# DoseManager.net
KiCad netlist of a schematic drawn in EAGLE
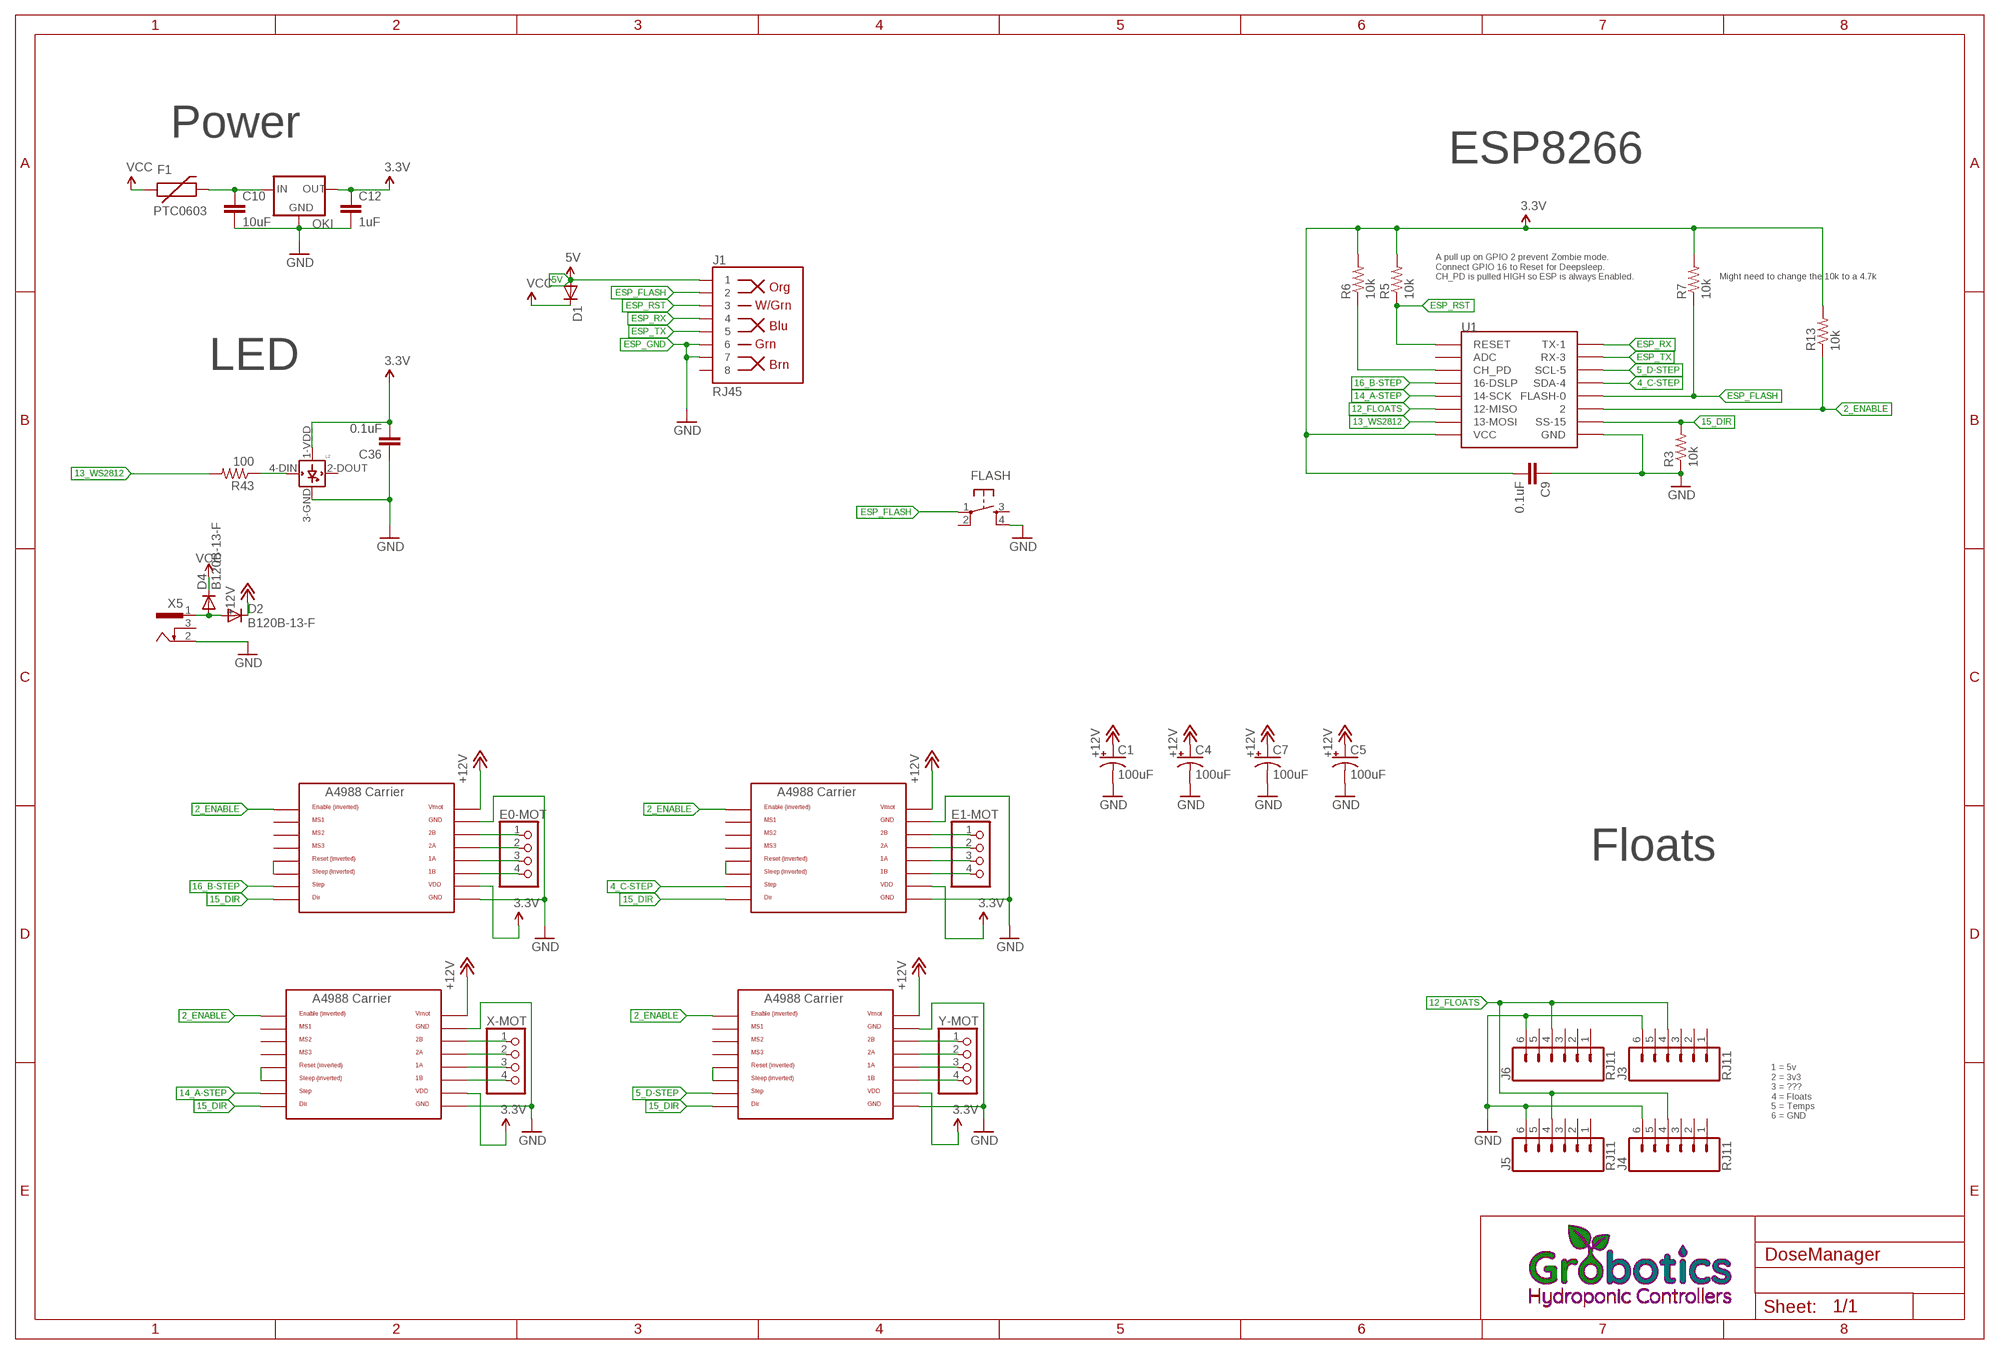
[diagram p0: schematic, sheet 1]

(export (version "E")
  (design (tool "Eeschema 10.0.6"))
  (components
    (comp (ref "C1")
      (value "100uF")
      (footprint "eagle-import:153CLV-0605")
      (libsource (lib "eagle-import") (part "CPOL-US153CLV-0605"))
    )
    (comp (ref "C4")
      (value "100uF")
      (footprint "eagle-import:153CLV-0605")
      (libsource (lib "eagle-import") (part "CPOL-US153CLV-0605"))
    )
    (comp (ref "C5")
      (value "100uF")
      (footprint "eagle-import:153CLV-0605")
      (libsource (lib "eagle-import") (part "CPOL-US153CLV-0605"))
    )
    (comp (ref "C7")
      (value "100uF")
      (footprint "eagle-import:153CLV-0605")
      (libsource (lib "eagle-import") (part "CPOL-US153CLV-0605"))
    )
    (comp (ref "C9")
      (value "0.1uF")
      (footprint "eagle-import:0805")
      (libsource (lib "eagle-import") (part "CAP0805"))
    )
    (comp (ref "C10")
      (value "10uF")
      (footprint "eagle-import:1206")
      (libsource (lib "eagle-import") (part "CAP1206"))
    )
    (comp (ref "C12")
      (value "1uF")
      (footprint "eagle-import:0805")
      (libsource (lib "eagle-import") (part "CAP0805"))
    )
    (comp (ref "C36")
      (value "0.1uF")
      (footprint "eagle-import:0805")
      (libsource (lib "eagle-import") (part "CAP0805"))
    )
    (comp (ref "D1")
      (value "DIODESOD")
      (footprint "eagle-import:SOD-323")
      (libsource (lib "eagle-import") (part "DIODESOD"))
    )
    (comp (ref "D2")
      (value "B120B-13-F")
      (footprint "eagle-import:SMB-DIODE")
      (libsource (lib "eagle-import") (part "DIODESMB"))
    )
    (comp (ref "D4")
      (value "B120B-13-F")
      (footprint "eagle-import:SMB-DIODE")
      (libsource (lib "eagle-import") (part "DIODESMB"))
    )
    (comp (ref "E0-MOT")
      (value "PINHD-1X4")
      (footprint "eagle-import:1X04")
      (libsource (lib "eagle-import") (part "PINHD-1X4"))
    )
    (comp (ref "E1-MOT")
      (value "PINHD-1X4")
      (footprint "eagle-import:1X04")
      (libsource (lib "eagle-import") (part "PINHD-1X4"))
    )
    (comp (ref "F1")
      (value "PTC0603")
      (footprint "eagle-import:0603")
      (libsource (lib "eagle-import") (part "PTC0603"))
    )
    (comp (ref "FLASH")
      (value "TAC_SWITCHSMD")
      (footprint "eagle-import:TACTILE_SWITCH_SMD")
      (libsource (lib "eagle-import") (part "TAC_SWITCHSMD"))
    )
    (comp (ref "J1")
      (value "RJ45")
      (footprint "eagle-import:RJ45-8")
      (libsource (lib "eagle-import") (part "RJ45-8"))
    )
    (comp (ref "J3")
      (value "RJ11")
      (footprint "eagle-import:RJ11-6")
      (fields (field (name "PROD_ID") "CONN-08590") (field (name "SF_ID") "PRT-00132"))
      (libsource (lib "eagle-import") (part "RJ11-6"))
    )
    (comp (ref "J4")
      (value "RJ11")
      (footprint "eagle-import:RJ11-6")
      (fields (field (name "PROD_ID") "CONN-08590") (field (name "SF_ID") "PRT-00132"))
      (libsource (lib "eagle-import") (part "RJ11-6"))
    )
    (comp (ref "J5")
      (value "RJ11")
      (footprint "eagle-import:RJ11-6")
      (fields (field (name "PROD_ID") "CONN-08590") (field (name "SF_ID") "PRT-00132"))
      (libsource (lib "eagle-import") (part "RJ11-6"))
    )
    (comp (ref "J6")
      (value "RJ11")
      (footprint "eagle-import:RJ11-6")
      (fields (field (name "PROD_ID") "CONN-08590") (field (name "SF_ID") "PRT-00132"))
      (libsource (lib "eagle-import") (part "RJ11-6"))
    )
    (comp (ref "L2")
      (value "WS2812B")
      (footprint "eagle-import:WS2812B")
      (libsource (lib "eagle-import") (part "WS2812B"))
    )
    (comp (ref "OKI")
      (value "78XXS")
      (footprint "eagle-import:78XXS")
      (libsource (lib "eagle-import") (part "78XXS"))
    )
    (comp (ref "R3")
      (value "10k")
      (footprint "eagle-import:0805")
      (libsource (lib "eagle-import") (part "RESISTOR0805"))
    )
    (comp (ref "R5")
      (value "10k")
      (footprint "eagle-import:0805")
      (libsource (lib "eagle-import") (part "RESISTOR0805"))
    )
    (comp (ref "R6")
      (value "10k")
      (footprint "eagle-import:0805")
      (libsource (lib "eagle-import") (part "RESISTOR0805"))
    )
    (comp (ref "R7")
      (value "10k")
      (footprint "eagle-import:0805")
      (libsource (lib "eagle-import") (part "RESISTOR0805"))
    )
    (comp (ref "R13")
      (value "10k")
      (footprint "eagle-import:0805")
      (libsource (lib "eagle-import") (part "RESISTOR0805"))
    )
    (comp (ref "R43")
      (value "100")
      (footprint "eagle-import:0805")
      (libsource (lib "eagle-import") (part "RESISTOR0805"))
    )
    (comp (ref "U$1")
      (value "A4988BREAKOUT")
      (footprint "eagle-import:A4988BREAKOUT")
      (libsource (lib "eagle-import") (part "A4988BREAKOUT"))
    )
    (comp (ref "U$2")
      (value "LOGO_GROBOTICS-S")
      (footprint "eagle-import:GROBOTICS-S")
      (libsource (lib "eagle-import") (part "LOGO_GROBOTICS-S"))
    )
    (comp (ref "U$5")
      (value "A4988BREAKOUT")
      (footprint "eagle-import:A4988BREAKOUT")
      (libsource (lib "eagle-import") (part "A4988BREAKOUT"))
    )
    (comp (ref "U$6")
      (value "A4988BREAKOUT")
      (footprint "eagle-import:A4988BREAKOUT")
      (libsource (lib "eagle-import") (part "A4988BREAKOUT"))
    )
    (comp (ref "U$7")
      (value "A4988BREAKOUT")
      (footprint "eagle-import:A4988BREAKOUT")
      (libsource (lib "eagle-import") (part "A4988BREAKOUT"))
    )
    (comp (ref "U1")
      (value "ESP12SMD")
      (footprint "eagle-import:ESP12-SMD")
      (libsource (lib "eagle-import") (part "ESP12SMD"))
    )
    (comp (ref "X-MOT")
      (value "PINHD-1X4")
      (footprint "eagle-import:1X04")
      (libsource (lib "eagle-import") (part "PINHD-1X4"))
    )
    (comp (ref "X5")
      (value "733980-62")
      (footprint "eagle-import:733980-62")
      (libsource (lib "eagle-import") (part "73398?0-62"))
    )
    (comp (ref "Y-MOT")
      (value "PINHD-1X4")
      (footprint "eagle-import:1X04")
      (libsource (lib "eagle-import") (part "PINHD-1X4"))
    )
  )
  (nets
    (net (code "1") (name "+12V") (class "Default")
      (node (ref "C1") (pin "+") (pinfunction "+_+") (pintype "passive"))
      (node (ref "C4") (pin "+") (pinfunction "+_+") (pintype "passive"))
      (node (ref "C5") (pin "+") (pinfunction "+_+") (pintype "passive"))
      (node (ref "C7") (pin "+") (pinfunction "+_+") (pintype "passive"))
      (node (ref "D2") (pin "C") (pinfunction "C_C") (pintype "passive"))
      (node (ref "U$1") (pin "VMOT") (pinfunction "VMOT_VMOT") (pintype "power_in"))
      (node (ref "U$5") (pin "VMOT") (pinfunction "VMOT_VMOT") (pintype "power_in"))
      (node (ref "U$6") (pin "VMOT") (pinfunction "VMOT_VMOT") (pintype "power_in"))
      (node (ref "U$7") (pin "VMOT") (pinfunction "VMOT_VMOT") (pintype "power_in"))
    )
    (net (code "2") (name "2_ENABLE") (class "Default")
      (node (ref "R13") (pin "1") (pinfunction "1_1") (pintype "passive"))
      (node (ref "U$1") (pin "EN") (pinfunction "EN_EN") (pintype "input"))
      (node (ref "U$5") (pin "EN") (pinfunction "EN_EN") (pintype "input"))
      (node (ref "U$6") (pin "EN") (pinfunction "EN_EN") (pintype "input"))
      (node (ref "U$7") (pin "EN") (pinfunction "EN_EN") (pintype "input"))
      (node (ref "U1") (pin "GPIO2") (pinfunction "2_GPIO2") (pintype "bidirectional"))
    )
    (net (code "3") (name "3.3V") (class "Default")
      (node (ref "C12") (pin "1") (pinfunction "1_1") (pintype "passive"))
      (node (ref "C36") (pin "2") (pinfunction "2_2") (pintype "passive"))
      (node (ref "C9") (pin "2") (pinfunction "2_2") (pintype "passive"))
      (node (ref "L2") (pin "1-VDD") (pinfunction "VDD_1-VDD") (pintype "bidirectional"))
      (node (ref "OKI") (pin "OUT") (pinfunction "OUT_OUT") (pintype "passive"))
      (node (ref "R13") (pin "2") (pinfunction "2_2") (pintype "passive"))
      (node (ref "R5") (pin "2") (pinfunction "2_2") (pintype "passive"))
      (node (ref "R6") (pin "2") (pinfunction "2_2") (pintype "passive"))
      (node (ref "R7") (pin "2") (pinfunction "2_2") (pintype "passive"))
      (node (ref "U$1") (pin "VDD") (pinfunction "VDD_VDD") (pintype "power_in"))
      (node (ref "U$5") (pin "VDD") (pinfunction "VDD_VDD") (pintype "power_in"))
      (node (ref "U$6") (pin "VDD") (pinfunction "VDD_VDD") (pintype "power_in"))
      (node (ref "U$7") (pin "VDD") (pinfunction "VDD_VDD") (pintype "power_in"))
      (node (ref "U1") (pin "VCC") (pinfunction "VCC_VCC") (pintype "bidirectional"))
    )
    (net (code "4") (name "4_C-STEP") (class "Default")
      (node (ref "U$5") (pin "STEP") (pinfunction "STEP_STEP") (pintype "input"))
      (node (ref "U1") (pin "GPIO4") (pinfunction "SDA-4_GPIO4") (pintype "bidirectional"))
    )
    (net (code "5") (name "5V") (class "Default")
      (node (ref "D1") (pin "2") (pinfunction "A_2") (pintype "passive"))
      (node (ref "J1") (pin "1") (pinfunction "1_1") (pintype "bidirectional"))
    )
    (net (code "6") (name "5_D-STEP") (class "Default")
      (node (ref "U$7") (pin "STEP") (pinfunction "STEP_STEP") (pintype "input"))
      (node (ref "U1") (pin "GPIO5") (pinfunction "SCL-5_GPIO5") (pintype "bidirectional"))
    )
    (net (code "7") (name "12_FLOATS") (class "Default")
      (node (ref "J3") (pin "4") (pinfunction "4_4") (pintype "passive"))
      (node (ref "J4") (pin "4") (pinfunction "4_4") (pintype "passive"))
      (node (ref "J5") (pin "4") (pinfunction "4_4") (pintype "passive"))
      (node (ref "J6") (pin "4") (pinfunction "4_4") (pintype "passive"))
      (node (ref "U1") (pin "GPIO12") (pinfunction "12-MISO_GPIO12") (pintype "bidirectional"))
    )
    (net (code "8") (name "13_WS2812") (class "Default")
      (node (ref "R43") (pin "2") (pinfunction "2_2") (pintype "passive"))
      (node (ref "U1") (pin "GPIO13") (pinfunction "13-MOSI_GPIO13") (pintype "bidirectional"))
    )
    (net (code "9") (name "14_A-STEP") (class "Default")
      (node (ref "U$6") (pin "STEP") (pinfunction "STEP_STEP") (pintype "input"))
      (node (ref "U1") (pin "GPIO14") (pinfunction "14-SCK_GPIO14") (pintype "bidirectional"))
    )
    (net (code "10") (name "15_DIR") (class "Default")
      (node (ref "R3") (pin "2") (pinfunction "2_2") (pintype "passive"))
      (node (ref "U$1") (pin "DIR") (pinfunction "DIR_DIR") (pintype "input"))
      (node (ref "U$5") (pin "DIR") (pinfunction "DIR_DIR") (pintype "input"))
      (node (ref "U$6") (pin "DIR") (pinfunction "DIR_DIR") (pintype "input"))
      (node (ref "U$7") (pin "DIR") (pinfunction "DIR_DIR") (pintype "input"))
      (node (ref "U1") (pin "GPIO15") (pinfunction "SS-15_GPIO15") (pintype "bidirectional"))
    )
    (net (code "11") (name "16_B-STEP") (class "Default")
      (node (ref "U$1") (pin "STEP") (pinfunction "STEP_STEP") (pintype "input"))
      (node (ref "U1") (pin "GPIO16") (pinfunction "16-DSLP_GPIO16") (pintype "bidirectional"))
    )
    (net (code "12") (name "ESP_FLASH") (class "Default")
      (node (ref "FLASH") (pin "1") (pinfunction "1_1") (pintype "passive"))
      (node (ref "J1") (pin "2") (pinfunction "2_2") (pintype "bidirectional"))
      (node (ref "R7") (pin "1") (pinfunction "1_1") (pintype "passive"))
      (node (ref "U1") (pin "GPIO0") (pinfunction "FLASH-0_GPIO0") (pintype "bidirectional"))
    )
    (net (code "13") (name "ESP_GND") (class "Default")
      (node (ref "C1") (pin "-") (pinfunction "-_-") (pintype "passive"))
      (node (ref "C10") (pin "2") (pinfunction "2_2") (pintype "passive"))
      (node (ref "C12") (pin "2") (pinfunction "2_2") (pintype "passive"))
      (node (ref "C36") (pin "1") (pinfunction "1_1") (pintype "passive"))
      (node (ref "C4") (pin "-") (pinfunction "-_-") (pintype "passive"))
      (node (ref "C5") (pin "-") (pinfunction "-_-") (pintype "passive"))
      (node (ref "C7") (pin "-") (pinfunction "-_-") (pintype "passive"))
      (node (ref "C9") (pin "1") (pinfunction "1_1") (pintype "passive"))
      (node (ref "FLASH") (pin "4") (pinfunction "4_4") (pintype "passive"))
      (node (ref "J1") (pin "6") (pinfunction "6_6") (pintype "bidirectional"))
      (node (ref "J1") (pin "7") (pinfunction "7_7") (pintype "bidirectional"))
      (node (ref "J3") (pin "6") (pinfunction "6_6") (pintype "passive"))
      (node (ref "J4") (pin "6") (pinfunction "6_6") (pintype "passive"))
      (node (ref "J5") (pin "6") (pinfunction "6_6") (pintype "passive"))
      (node (ref "J6") (pin "6") (pinfunction "6_6") (pintype "passive"))
      (node (ref "L2") (pin "3-GND") (pinfunction "GND_3-GND") (pintype "bidirectional"))
      (node (ref "OKI") (pin "GND") (pinfunction "GND_GND") (pintype "input"))
      (node (ref "R3") (pin "1") (pinfunction "1_1") (pintype "passive"))
      (node (ref "U$1") (pin "GND") (pinfunction "GND_GND") (pintype "power_in"))
      (node (ref "U$1") (pin "GND@0") (pinfunction "GND_GND@0") (pintype "power_in"))
      (node (ref "U$5") (pin "GND") (pinfunction "GND_GND") (pintype "power_in"))
      (node (ref "U$5") (pin "GND@0") (pinfunction "GND_GND@0") (pintype "power_in"))
      (node (ref "U$6") (pin "GND") (pinfunction "GND_GND") (pintype "power_in"))
      (node (ref "U$6") (pin "GND@0") (pinfunction "GND_GND@0") (pintype "power_in"))
      (node (ref "U$7") (pin "GND") (pinfunction "GND_GND") (pintype "power_in"))
      (node (ref "U$7") (pin "GND@0") (pinfunction "GND_GND@0") (pintype "power_in"))
      (node (ref "U1") (pin "GND") (pinfunction "GND_GND") (pintype "bidirectional"))
      (node (ref "X5") (pin "2") (pinfunction "2_2") (pintype "passive"))
    )
    (net (code "14") (name "ESP_RST") (class "Default")
      (node (ref "J1") (pin "3") (pinfunction "3_3") (pintype "bidirectional"))
      (node (ref "R5") (pin "1") (pinfunction "1_1") (pintype "passive"))
      (node (ref "U1") (pin "RESET") (pinfunction "RESET_RESET") (pintype "bidirectional"))
    )
    (net (code "15") (name "ESP_RX") (class "Default")
      (node (ref "J1") (pin "4") (pinfunction "4_4") (pintype "bidirectional"))
      (node (ref "U1") (pin "TXD0") (pinfunction "TX-1_TXD0") (pintype "bidirectional"))
    )
    (net (code "16") (name "ESP_TX") (class "Default")
      (node (ref "J1") (pin "5") (pinfunction "5_5") (pintype "bidirectional"))
      (node (ref "U1") (pin "RXD0") (pinfunction "RX-3_RXD0") (pintype "bidirectional"))
    )
    (net (code "17") (name "Net-(C10-Pad1)") (class "Default")
      (node (ref "C10") (pin "1") (pinfunction "1_1") (pintype "passive"))
      (node (ref "F1") (pin "2") (pinfunction "2_2") (pintype "bidirectional"))
      (node (ref "OKI") (pin "IN") (pinfunction "IN_IN") (pintype "input"))
    )
    (net (code "18") (name "Net-(D2-PadA)") (class "Default")
      (node (ref "D2") (pin "A") (pinfunction "A_A") (pintype "passive"))
      (node (ref "D4") (pin "A") (pinfunction "A_A") (pintype "passive"))
      (node (ref "X5") (pin "1") (pinfunction "1_1") (pintype "passive"))
    )
    (net (code "19") (name "Net-(E0-MOT-Pad1)") (class "Default")
      (node (ref "E0-MOT") (pin "1") (pinfunction "1_1") (pintype "passive"))
      (node (ref "U$1") (pin "2B") (pinfunction "2B_2B") (pintype "output"))
    )
    (net (code "20") (name "Net-(E0-MOT-Pad2)") (class "Default")
      (node (ref "E0-MOT") (pin "2") (pinfunction "2_2") (pintype "passive"))
      (node (ref "U$1") (pin "2A") (pinfunction "2A_2A") (pintype "output"))
    )
    (net (code "21") (name "Net-(E0-MOT-Pad3)") (class "Default")
      (node (ref "E0-MOT") (pin "3") (pinfunction "3_3") (pintype "passive"))
      (node (ref "U$1") (pin "1A") (pinfunction "1A_1A") (pintype "output"))
    )
    (net (code "22") (name "Net-(E0-MOT-Pad4)") (class "Default")
      (node (ref "E0-MOT") (pin "4") (pinfunction "4_4") (pintype "passive"))
      (node (ref "U$1") (pin "1B") (pinfunction "1B_1B") (pintype "output"))
    )
    (net (code "23") (name "Net-(E1-MOT-Pad1)") (class "Default")
      (node (ref "E1-MOT") (pin "1") (pinfunction "1_1") (pintype "passive"))
      (node (ref "U$5") (pin "2B") (pinfunction "2B_2B") (pintype "output"))
    )
    (net (code "24") (name "Net-(E1-MOT-Pad2)") (class "Default")
      (node (ref "E1-MOT") (pin "2") (pinfunction "2_2") (pintype "passive"))
      (node (ref "U$5") (pin "2A") (pinfunction "2A_2A") (pintype "output"))
    )
    (net (code "25") (name "Net-(E1-MOT-Pad3)") (class "Default")
      (node (ref "E1-MOT") (pin "3") (pinfunction "3_3") (pintype "passive"))
      (node (ref "U$5") (pin "1A") (pinfunction "1A_1A") (pintype "output"))
    )
    (net (code "26") (name "Net-(E1-MOT-Pad4)") (class "Default")
      (node (ref "E1-MOT") (pin "4") (pinfunction "4_4") (pintype "passive"))
      (node (ref "U$5") (pin "1B") (pinfunction "1B_1B") (pintype "output"))
    )
    (net (code "27") (name "Net-(L2-DIN)") (class "Default")
      (node (ref "L2") (pin "4-DIN") (pinfunction "DIN_4-DIN") (pintype "input"))
      (node (ref "R43") (pin "1") (pinfunction "1_1") (pintype "passive"))
    )
    (net (code "28") (name "Net-(R6-Pad1)") (class "Default")
      (node (ref "R6") (pin "1") (pinfunction "1_1") (pintype "passive"))
      (node (ref "U1") (pin "CH_PD") (pinfunction "CH_PD_CH_PD") (pintype "bidirectional"))
    )
    (net (code "29") (name "Net-(U$1-SLEEP)") (class "Default")
      (node (ref "U$1") (pin "RST") (pinfunction "RST_RST") (pintype "input"))
      (node (ref "U$1") (pin "SLP") (pinfunction "SLEEP_SLP") (pintype "input"))
    )
    (net (code "30") (name "Net-(U$5-SLEEP)") (class "Default")
      (node (ref "U$5") (pin "RST") (pinfunction "RST_RST") (pintype "input"))
      (node (ref "U$5") (pin "SLP") (pinfunction "SLEEP_SLP") (pintype "input"))
    )
    (net (code "31") (name "Net-(U$6-Pad1A)") (class "Default")
      (node (ref "U$6") (pin "1A") (pinfunction "1A_1A") (pintype "output"))
      (node (ref "X-MOT") (pin "3") (pinfunction "3_3") (pintype "passive"))
    )
    (net (code "32") (name "Net-(U$6-Pad1B)") (class "Default")
      (node (ref "U$6") (pin "1B") (pinfunction "1B_1B") (pintype "output"))
      (node (ref "X-MOT") (pin "4") (pinfunction "4_4") (pintype "passive"))
    )
    (net (code "33") (name "Net-(U$6-Pad2A)") (class "Default")
      (node (ref "U$6") (pin "2A") (pinfunction "2A_2A") (pintype "output"))
      (node (ref "X-MOT") (pin "2") (pinfunction "2_2") (pintype "passive"))
    )
    (net (code "34") (name "Net-(U$6-Pad2B)") (class "Default")
      (node (ref "U$6") (pin "2B") (pinfunction "2B_2B") (pintype "output"))
      (node (ref "X-MOT") (pin "1") (pinfunction "1_1") (pintype "passive"))
    )
    (net (code "35") (name "Net-(U$6-SLEEP)") (class "Default")
      (node (ref "U$6") (pin "RST") (pinfunction "RST_RST") (pintype "input"))
      (node (ref "U$6") (pin "SLP") (pinfunction "SLEEP_SLP") (pintype "input"))
    )
    (net (code "36") (name "Net-(U$7-Pad1A)") (class "Default")
      (node (ref "U$7") (pin "1A") (pinfunction "1A_1A") (pintype "output"))
      (node (ref "Y-MOT") (pin "3") (pinfunction "3_3") (pintype "passive"))
    )
    (net (code "37") (name "Net-(U$7-Pad1B)") (class "Default")
      (node (ref "U$7") (pin "1B") (pinfunction "1B_1B") (pintype "output"))
      (node (ref "Y-MOT") (pin "4") (pinfunction "4_4") (pintype "passive"))
    )
    (net (code "38") (name "Net-(U$7-Pad2A)") (class "Default")
      (node (ref "U$7") (pin "2A") (pinfunction "2A_2A") (pintype "output"))
      (node (ref "Y-MOT") (pin "2") (pinfunction "2_2") (pintype "passive"))
    )
    (net (code "39") (name "Net-(U$7-Pad2B)") (class "Default")
      (node (ref "U$7") (pin "2B") (pinfunction "2B_2B") (pintype "output"))
      (node (ref "Y-MOT") (pin "1") (pinfunction "1_1") (pintype "passive"))
    )
    (net (code "40") (name "Net-(U$7-SLEEP)") (class "Default")
      (node (ref "U$7") (pin "RST") (pinfunction "RST_RST") (pintype "input"))
      (node (ref "U$7") (pin "SLP") (pinfunction "SLEEP_SLP") (pintype "input"))
    )
    (net (code "41") (name "VCC") (class "Default")
      (node (ref "D1") (pin "1") (pinfunction "C_1") (pintype "passive"))
      (node (ref "D4") (pin "C") (pinfunction "C_C") (pintype "passive"))
      (node (ref "F1") (pin "1") (pinfunction "1_1") (pintype "bidirectional"))
    )
    (net (code "42") (name "unconnected-(FLASH-Pad2)") (class "Default")
      (node (ref "FLASH") (pin "2") (pinfunction "2_2") (pintype "passive"))
    )
    (net (code "43") (name "unconnected-(FLASH-Pad3)") (class "Default")
      (node (ref "FLASH") (pin "3") (pinfunction "3_3") (pintype "passive"))
    )
    (net (code "44") (name "unconnected-(J1-Pad8)") (class "Default")
      (node (ref "J1") (pin "8") (pinfunction "8_8") (pintype "bidirectional"))
    )
    (net (code "45") (name "unconnected-(J3-Pad1)") (class "Default")
      (node (ref "J3") (pin "1") (pinfunction "1_1") (pintype "passive"))
    )
    (net (code "46") (name "unconnected-(J3-Pad2)") (class "Default")
      (node (ref "J3") (pin "2") (pinfunction "2_2") (pintype "passive"))
    )
    (net (code "47") (name "unconnected-(J3-Pad3)") (class "Default")
      (node (ref "J3") (pin "3") (pinfunction "3_3") (pintype "passive"))
    )
    (net (code "48") (name "unconnected-(J3-Pad5)") (class "Default")
      (node (ref "J3") (pin "5") (pinfunction "5_5") (pintype "passive"))
    )
    (net (code "49") (name "unconnected-(J4-Pad1)") (class "Default")
      (node (ref "J4") (pin "1") (pinfunction "1_1") (pintype "passive"))
    )
    (net (code "50") (name "unconnected-(J4-Pad2)") (class "Default")
      (node (ref "J4") (pin "2") (pinfunction "2_2") (pintype "passive"))
    )
    (net (code "51") (name "unconnected-(J4-Pad3)") (class "Default")
      (node (ref "J4") (pin "3") (pinfunction "3_3") (pintype "passive"))
    )
    (net (code "52") (name "unconnected-(J4-Pad5)") (class "Default")
      (node (ref "J4") (pin "5") (pinfunction "5_5") (pintype "passive"))
    )
    (net (code "53") (name "unconnected-(J5-Pad1)") (class "Default")
      (node (ref "J5") (pin "1") (pinfunction "1_1") (pintype "passive"))
    )
    (net (code "54") (name "unconnected-(J5-Pad2)") (class "Default")
      (node (ref "J5") (pin "2") (pinfunction "2_2") (pintype "passive"))
    )
    (net (code "55") (name "unconnected-(J5-Pad3)") (class "Default")
      (node (ref "J5") (pin "3") (pinfunction "3_3") (pintype "passive"))
    )
    (net (code "56") (name "unconnected-(J5-Pad5)") (class "Default")
      (node (ref "J5") (pin "5") (pinfunction "5_5") (pintype "passive"))
    )
    (net (code "57") (name "unconnected-(J6-Pad1)") (class "Default")
      (node (ref "J6") (pin "1") (pinfunction "1_1") (pintype "passive"))
    )
    (net (code "58") (name "unconnected-(J6-Pad2)") (class "Default")
      (node (ref "J6") (pin "2") (pinfunction "2_2") (pintype "passive"))
    )
    (net (code "59") (name "unconnected-(J6-Pad3)") (class "Default")
      (node (ref "J6") (pin "3") (pinfunction "3_3") (pintype "passive"))
    )
    (net (code "60") (name "unconnected-(J6-Pad5)") (class "Default")
      (node (ref "J6") (pin "5") (pinfunction "5_5") (pintype "passive"))
    )
    (net (code "61") (name "unconnected-(L2-DOUT-Pad2-DOUT)") (class "Default")
      (node (ref "L2") (pin "2-DOUT") (pinfunction "DOUT_2-DOUT") (pintype "output"))
    )
    (net (code "62") (name "unconnected-(U$1-PadMS1)") (class "Default")
      (node (ref "U$1") (pin "MS1") (pinfunction "MS1_MS1") (pintype "input"))
    )
    (net (code "63") (name "unconnected-(U$1-PadMS2)") (class "Default")
      (node (ref "U$1") (pin "MS2") (pinfunction "MS2_MS2") (pintype "input"))
    )
    (net (code "64") (name "unconnected-(U$1-PadMS3)") (class "Default")
      (node (ref "U$1") (pin "MS3") (pinfunction "MS3_MS3") (pintype "input"))
    )
    (net (code "65") (name "unconnected-(U$5-PadMS1)") (class "Default")
      (node (ref "U$5") (pin "MS1") (pinfunction "MS1_MS1") (pintype "input"))
    )
    (net (code "66") (name "unconnected-(U$5-PadMS2)") (class "Default")
      (node (ref "U$5") (pin "MS2") (pinfunction "MS2_MS2") (pintype "input"))
    )
    (net (code "67") (name "unconnected-(U$5-PadMS3)") (class "Default")
      (node (ref "U$5") (pin "MS3") (pinfunction "MS3_MS3") (pintype "input"))
    )
    (net (code "68") (name "unconnected-(U$6-PadMS1)") (class "Default")
      (node (ref "U$6") (pin "MS1") (pinfunction "MS1_MS1") (pintype "input"))
    )
    (net (code "69") (name "unconnected-(U$6-PadMS2)") (class "Default")
      (node (ref "U$6") (pin "MS2") (pinfunction "MS2_MS2") (pintype "input"))
    )
    (net (code "70") (name "unconnected-(U$6-PadMS3)") (class "Default")
      (node (ref "U$6") (pin "MS3") (pinfunction "MS3_MS3") (pintype "input"))
    )
    (net (code "71") (name "unconnected-(U$7-PadMS1)") (class "Default")
      (node (ref "U$7") (pin "MS1") (pinfunction "MS1_MS1") (pintype "input"))
    )
    (net (code "72") (name "unconnected-(U$7-PadMS2)") (class "Default")
      (node (ref "U$7") (pin "MS2") (pinfunction "MS2_MS2") (pintype "input"))
    )
    (net (code "73") (name "unconnected-(U$7-PadMS3)") (class "Default")
      (node (ref "U$7") (pin "MS3") (pinfunction "MS3_MS3") (pintype "input"))
    )
    (net (code "74") (name "unconnected-(U1-PadADC)") (class "Default")
      (node (ref "U1") (pin "ADC") (pinfunction "ADC_ADC") (pintype "bidirectional"))
    )
    (net (code "75") (name "unconnected-(X5-Pad3)") (class "Default")
      (node (ref "X5") (pin "3") (pinfunction "3_3") (pintype "passive"))
    )
  )
)
